# GPS_test.net
KiCad netlist of a schematic drawn in Altium Designer
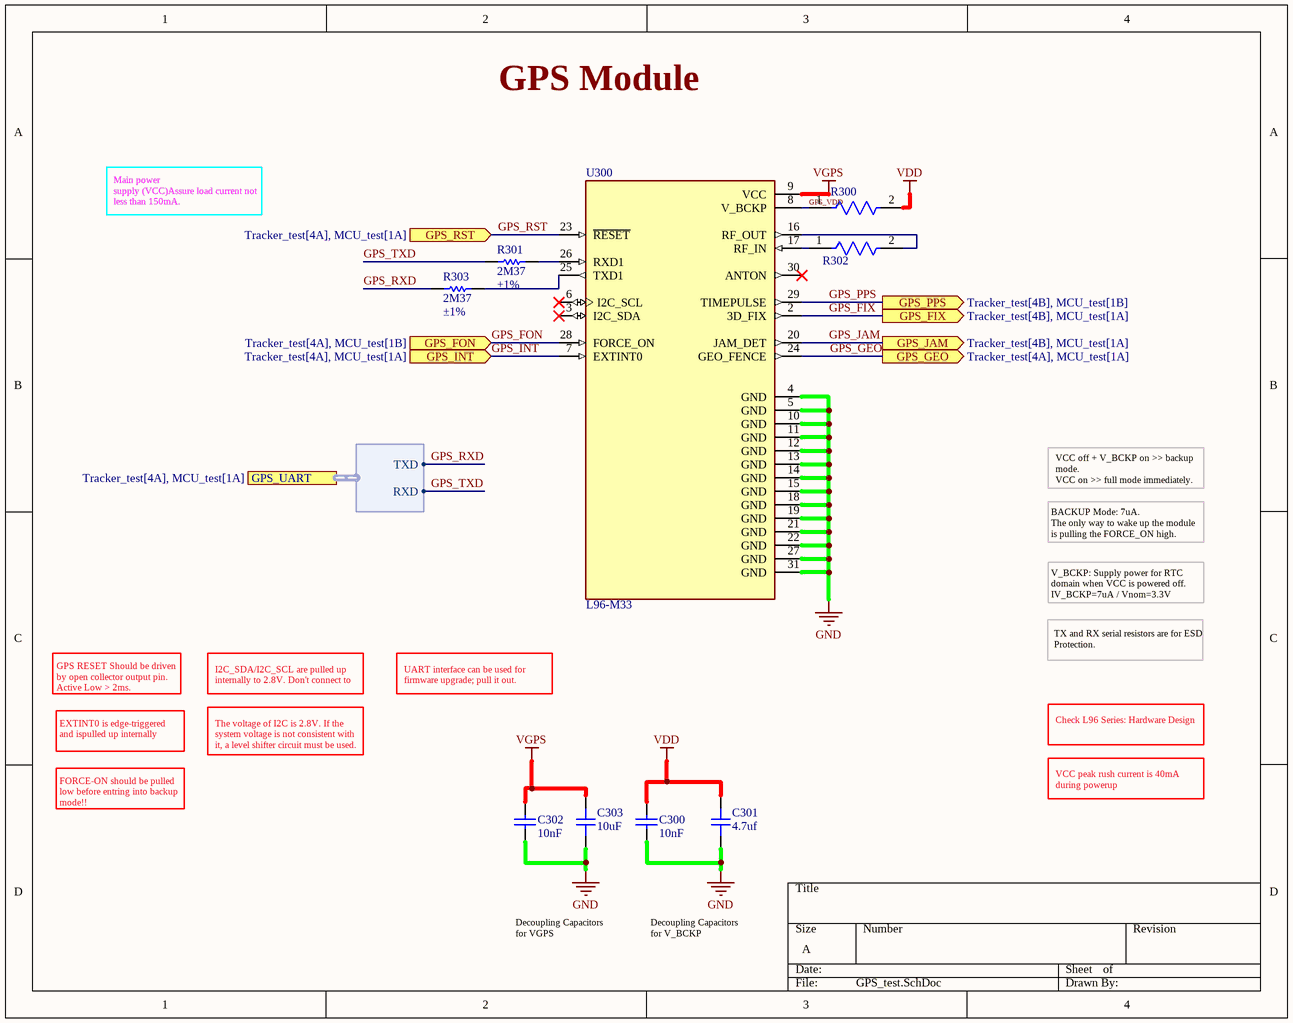
[diagram p0: GPS_test.SchDoc]

(export (version "E")
  (design (tool "Eeschema 10.0.6"))
  (components
    (comp (ref "C300")
      (value "10nF")
      (footprint "C0402 - duplicate")
      (description "CAP CER 0.1UF 10V X7R 0603")
      (fields
        (field (name "PART NUMBER") "C00062")
        (field (name "MANUFACTURER") "KEMET - Electronic Component")
      )
      (libsource (lib "intrgrat_lib") (part "CAP"))
    )
    (comp (ref "C301")
      (value "4.7uf")
      (footprint "CAP_0402")
      (description "Capacitor SMD 0402")
      (libsource (lib "PhilsLab_Library") (part "CAP_0402"))
    )
    (comp (ref "C302")
      (value "10nF")
      (footprint "C0402 - duplicate")
      (description "CAP CER 0.1UF 10V X7R 0603")
      (fields
        (field (name "PART NUMBER") "C00062")
        (field (name "MANUFACTURER") "KEMET - Electronic Component")
      )
      (libsource (lib "intrgrat_lib") (part "CAP"))
    )
    (comp (ref "C303")
      (value "10uF")
      (footprint "CAP_0402")
      (description "Capacitor SMD 0402")
      (libsource (lib "PhilsLab_Library") (part "CAP_0402"))
    )
    (comp (ref "R300")
      (value "AF0402JR-070RL")
      (footprint "FP-AF0402-IPC_A")
      (description "Anti-Sulfurated Chip Resistors Automotive Grade 0Ω 0402")
      (fields (field (name "TOLERANCE") "5%"))
      (libsource (lib "intrgrat_lib") (part "CMP-03412-048355-1"))
    )
    (comp (ref "R301")
      (value "2M37")
      (footprint "R0402")
      (description "RES SMD 15 OHM 1% 1/10W 0603")
      (fields
        (field (name "PART NUMBER") "R00007")
        (field (name "MANUFACTURER") "Yageo")
        (field (name "TOLERANCE") "±1%")
      )
      (libsource (lib "intrgrat_lib") (part "RES"))
    )
    (comp (ref "R302")
      (value "AF0402JR-070RL")
      (footprint "FP-AF0402-IPC_A")
      (description "Anti-Sulfurated Chip Resistors Automotive Grade 0Ω 0402")
      (fields (field (name "TOLERANCE") "5%"))
      (libsource (lib "intrgrat_lib") (part "CMP-03412-048355-1"))
    )
    (comp (ref "R303")
      (value "2M37")
      (footprint "R0402")
      (description "RES SMD 15 OHM 1% 1/10W 0603")
      (fields
        (field (name "PART NUMBER") "R00007")
        (field (name "MANUFACTURER") "Yageo")
        (field (name "TOLERANCE") "±1%")
      )
      (libsource (lib "intrgrat_lib") (part "RES"))
    )
    (comp (ref "U300")
      (value "L96-M33")
      (footprint "intrgrat_lib:XCVR_L96-M33")
      (fields (field (name "MF") "Quectel"))
      (libsource (lib "intrgrat_lib") (part "L96-M33"))
    )
  )
  (nets
    (net (code "2") (name "/GPS_FIX") (class "Default")
      (node (ref "U300") (pin "2") (pinfunction "3D_FIX_2") (pintype "output"))
    )
    (net (code "3") (name "/GPS_FON") (class "Default")
      (node (ref "U300") (pin "28") (pinfunction "FORCE_ON_28") (pintype "input"))
    )
    (net (code "4") (name "/GPS_GEO") (class "Default")
      (node (ref "U300") (pin "24") (pinfunction "GEO_FENCE_24") (pintype "output"))
    )
    (net (code "5") (name "/GPS_INT") (class "Default")
      (node (ref "U300") (pin "7") (pinfunction "EXTINT0_7") (pintype "input"))
    )
    (net (code "6") (name "/GPS_JAM") (class "Default")
      (node (ref "U300") (pin "20") (pinfunction "JAM_DET_20") (pintype "output"))
    )
    (net (code "7") (name "/GPS_PPS") (class "Default")
      (node (ref "U300") (pin "29") (pinfunction "TIMEPULSE_29") (pintype "output"))
    )
    (net (code "8") (name "/GPS_RST") (class "Default")
      (node (ref "U300") (pin "23") (pinfunction "~{RESET}_23") (pintype "input"))
    )
    (net (code "9") (name "/GPS_RXD") (class "Default")
      (node (ref "R303") (pin "1") (pinfunction "1_1") (pintype "passive"))
    )
    (net (code "10") (name "/GPS_TXD") (class "Default")
      (node (ref "R301") (pin "1") (pinfunction "1_1") (pintype "passive"))
    )
    (net (code "11") (name "/GPS_VDD") (class "Default")
      (node (ref "R300") (pin "1") (pinfunction "1_1") (pintype "passive"))
      (node (ref "U300") (pin "8") (pinfunction "V_BCKP_8") (pintype "power_in"))
    )
    (net (code "13") (name "GND") (class "Default")
      (node (ref "C300") (pin "2") (pinfunction "2_2") (pintype "passive"))
      (node (ref "C301") (pin "1") (pinfunction "1_1") (pintype "passive"))
      (node (ref "C302") (pin "2") (pinfunction "2_2") (pintype "passive"))
      (node (ref "C303") (pin "1") (pinfunction "1_1") (pintype "passive"))
      (node (ref "U300") (pin "10") (pinfunction "GND_10") (pintype "power_in"))
      (node (ref "U300") (pin "11") (pinfunction "GND_11") (pintype "power_in"))
      (node (ref "U300") (pin "12") (pinfunction "GND_12") (pintype "power_in"))
      (node (ref "U300") (pin "13") (pinfunction "GND_13") (pintype "power_in"))
      (node (ref "U300") (pin "14") (pinfunction "GND_14") (pintype "power_in"))
      (node (ref "U300") (pin "15") (pinfunction "GND_15") (pintype "power_in"))
      (node (ref "U300") (pin "18") (pinfunction "GND_18") (pintype "power_in"))
      (node (ref "U300") (pin "19") (pinfunction "GND_19") (pintype "power_in"))
      (node (ref "U300") (pin "21") (pinfunction "GND_21") (pintype "power_in"))
      (node (ref "U300") (pin "22") (pinfunction "GND_22") (pintype "power_in"))
      (node (ref "U300") (pin "27") (pinfunction "GND_27") (pintype "power_in"))
      (node (ref "U300") (pin "31") (pinfunction "GND_31") (pintype "power_in"))
      (node (ref "U300") (pin "4") (pinfunction "GND_4") (pintype "power_in"))
      (node (ref "U300") (pin "5") (pinfunction "GND_5") (pintype "power_in"))
    )
    (net (code "14") (name "Net-(U300-RF_IN)") (class "Default")
      (node (ref "R302") (pin "1") (pinfunction "1_1") (pintype "passive"))
      (node (ref "U300") (pin "17") (pinfunction "RF_IN_17") (pintype "input"))
    )
    (net (code "15") (name "Net-(U300-RF_OUT)") (class "Default")
      (node (ref "R302") (pin "2") (pinfunction "2_2") (pintype "passive"))
      (node (ref "U300") (pin "16") (pinfunction "RF_OUT_16") (pintype "output"))
    )
    (net (code "16") (name "Net-(U300-RXD1)") (class "Default")
      (node (ref "R301") (pin "2") (pinfunction "2_2") (pintype "passive"))
      (node (ref "U300") (pin "26") (pinfunction "RXD1_26") (pintype "input"))
    )
    (net (code "17") (name "Net-(U300-TXD1)") (class "Default")
      (node (ref "R303") (pin "2") (pinfunction "2_2") (pintype "passive"))
      (node (ref "U300") (pin "25") (pinfunction "TXD1_25") (pintype "output"))
    )
    (net (code "18") (name "VDD") (class "Default")
      (node (ref "C300") (pin "1") (pinfunction "1_1") (pintype "passive"))
      (node (ref "C301") (pin "2") (pinfunction "2_2") (pintype "passive"))
      (node (ref "R300") (pin "2") (pinfunction "2_2") (pintype "passive"))
    )
    (net (code "19") (name "VGPS") (class "Default")
      (node (ref "C302") (pin "1") (pinfunction "1_1") (pintype "passive"))
      (node (ref "C303") (pin "2") (pinfunction "2_2") (pintype "passive"))
      (node (ref "U300") (pin "9") (pinfunction "VCC_9") (pintype "power_in"))
    )
    (net (code "20") (name "unconnected-(U300-ANTON-Pad30)") (class "Default")
      (node (ref "U300") (pin "30") (pinfunction "ANTON_30") (pintype "output+no_connect"))
    )
    (net (code "21") (name "unconnected-(U300-I2C_SCL-Pad6)") (class "Default")
      (node (ref "U300") (pin "6") (pinfunction "I2C_SCL_6") (pintype "bidirectional+no_connect"))
    )
    (net (code "22") (name "unconnected-(U300-I2C_SDA-Pad3)") (class "Default")
      (node (ref "U300") (pin "3") (pinfunction "I2C_SDA_3") (pintype "bidirectional+no_connect"))
    )
  )
)
